# prc20breakout.net
KiCad netlist of a schematic drawn in EAGLE
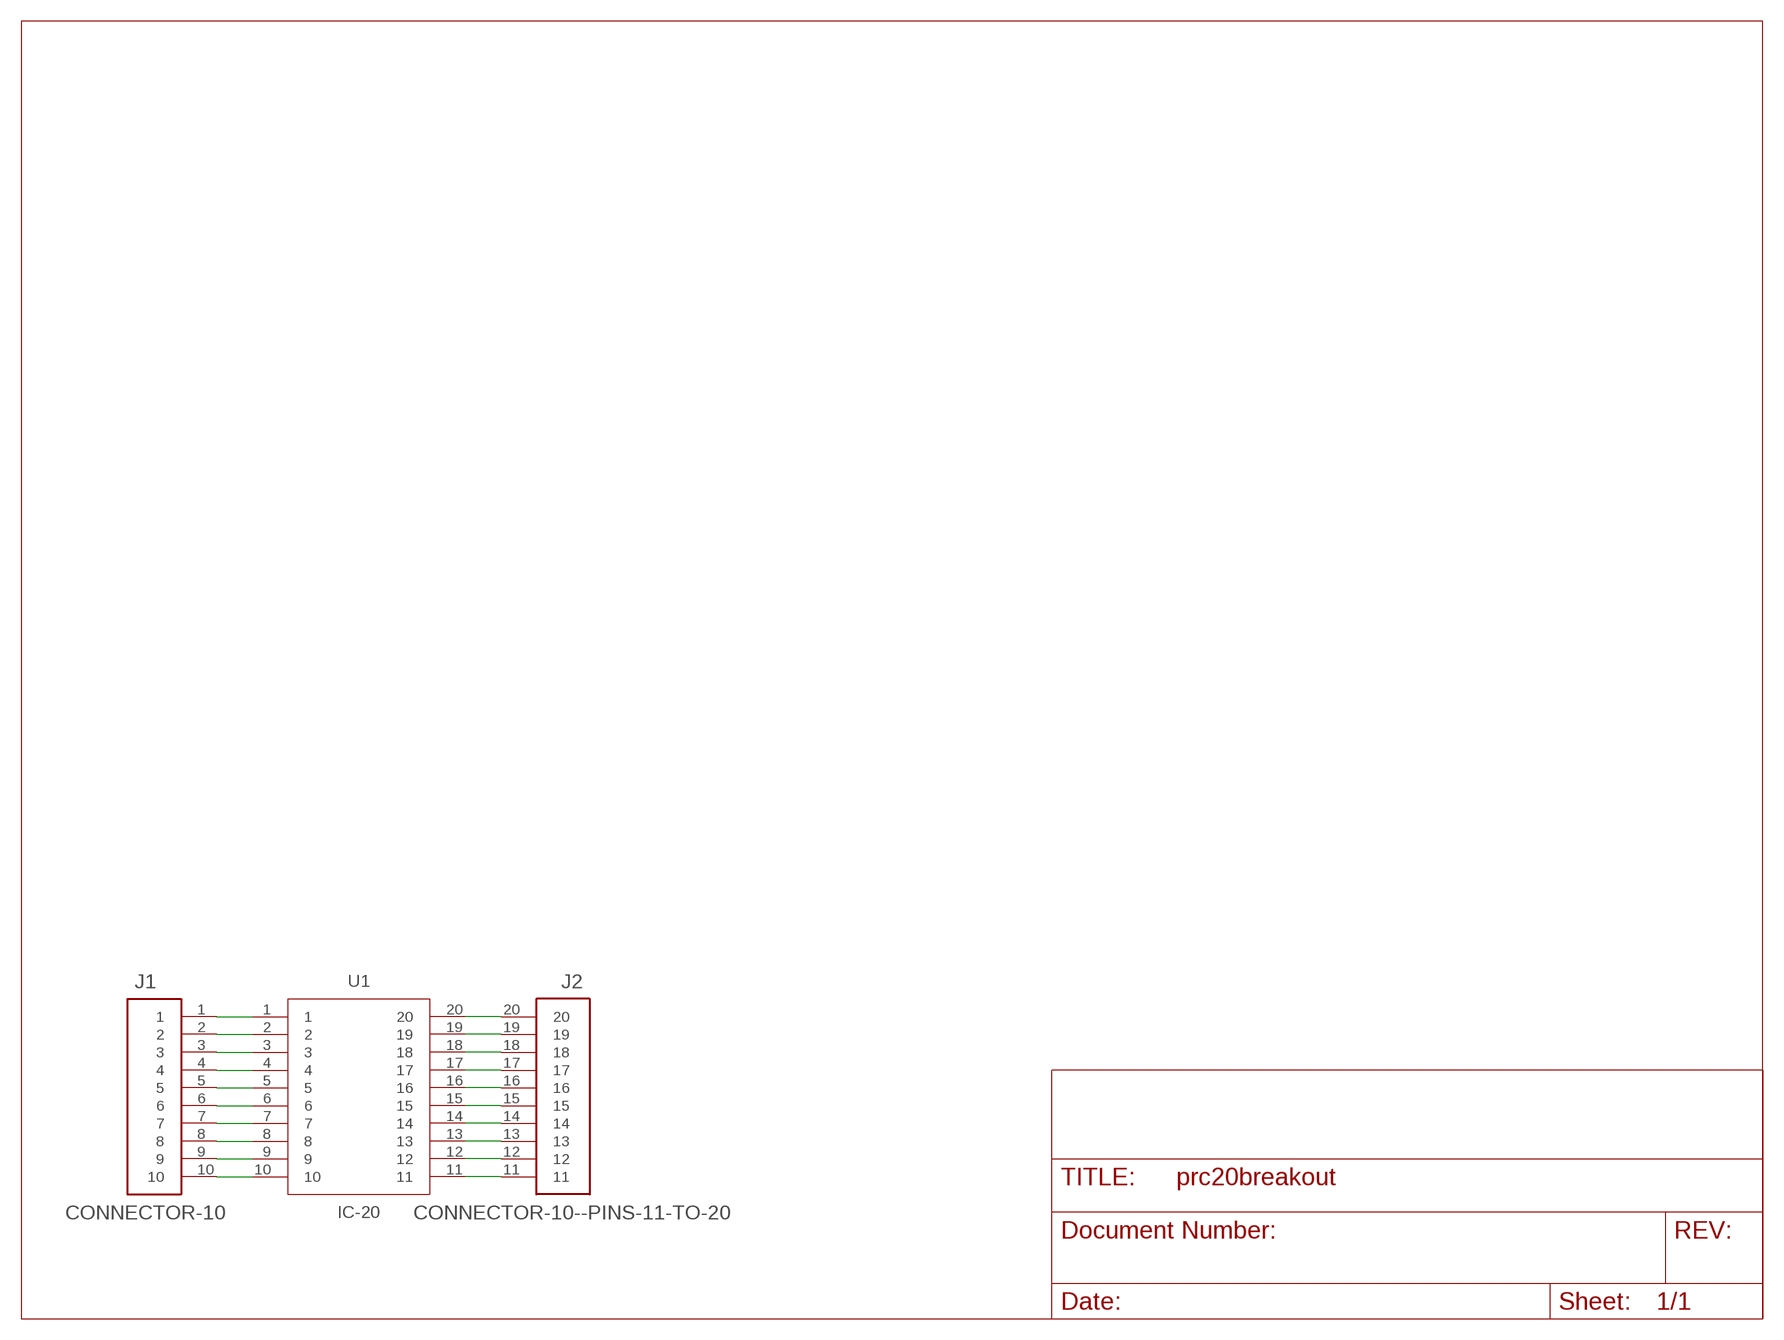
[diagram p0: schematic, sheet 1]

(export (version "E")
  (design (tool "Eeschema 10.0.6"))
  (components
    (comp (ref "J1")
      (value "CONNECTOR-10")
      (footprint "eagle-import:ESQ-110-XX-XX-S")
      (libsource (lib "eagle-import") (part "CONNECTOR-10"))
    )
    (comp (ref "J2")
      (value "CONNECTOR-10--PINS-11-TO-20")
      (footprint "eagle-import:ESQ-110-XX-XX-S--ROUND-PIN-1")
      (libsource (lib "eagle-import") (part "CONNECTOR-10--PINS-11-TO-20"))
    )
    (comp (ref "U1")
      (value "IC-20")
      (footprint "eagle-import:PLCC127P990X990X457-20N")
      (libsource (lib "eagle-import") (part "IC-20"))
    )
  )
  (nets
    (net (code "1") (name "Net-(J1-Pad1)") (class "Default")
      (node (ref "J1") (pin "1") (pinfunction "1_1") (pintype "bidirectional"))
      (node (ref "U1") (pin "1") (pinfunction "1_1") (pintype "bidirectional"))
    )
    (net (code "2") (name "Net-(J1-Pad2)") (class "Default")
      (node (ref "J1") (pin "2") (pinfunction "2_2") (pintype "bidirectional"))
      (node (ref "U1") (pin "2") (pinfunction "2_2") (pintype "bidirectional"))
    )
    (net (code "3") (name "Net-(J1-Pad3)") (class "Default")
      (node (ref "J1") (pin "3") (pinfunction "3_3") (pintype "bidirectional"))
      (node (ref "U1") (pin "3") (pinfunction "3_3") (pintype "bidirectional"))
    )
    (net (code "4") (name "Net-(J1-Pad4)") (class "Default")
      (node (ref "J1") (pin "4") (pinfunction "4_4") (pintype "bidirectional"))
      (node (ref "U1") (pin "4") (pinfunction "4_4") (pintype "bidirectional"))
    )
    (net (code "5") (name "Net-(J1-Pad5)") (class "Default")
      (node (ref "J1") (pin "5") (pinfunction "5_5") (pintype "bidirectional"))
      (node (ref "U1") (pin "5") (pinfunction "5_5") (pintype "bidirectional"))
    )
    (net (code "6") (name "Net-(J1-Pad6)") (class "Default")
      (node (ref "J1") (pin "6") (pinfunction "6_6") (pintype "bidirectional"))
      (node (ref "U1") (pin "6") (pinfunction "6_6") (pintype "bidirectional"))
    )
    (net (code "7") (name "Net-(J1-Pad7)") (class "Default")
      (node (ref "J1") (pin "7") (pinfunction "7_7") (pintype "bidirectional"))
      (node (ref "U1") (pin "7") (pinfunction "7_7") (pintype "bidirectional"))
    )
    (net (code "8") (name "Net-(J1-Pad8)") (class "Default")
      (node (ref "J1") (pin "8") (pinfunction "8_8") (pintype "bidirectional"))
      (node (ref "U1") (pin "8") (pinfunction "8_8") (pintype "bidirectional"))
    )
    (net (code "9") (name "Net-(J1-Pad9)") (class "Default")
      (node (ref "J1") (pin "9") (pinfunction "9_9") (pintype "bidirectional"))
      (node (ref "U1") (pin "9") (pinfunction "9_9") (pintype "bidirectional"))
    )
    (net (code "10") (name "Net-(J1-Pad10)") (class "Default")
      (node (ref "J1") (pin "10") (pinfunction "10_10") (pintype "bidirectional"))
      (node (ref "U1") (pin "10") (pinfunction "10_10") (pintype "bidirectional"))
    )
    (net (code "11") (name "Net-(J2-Pad11)") (class "Default")
      (node (ref "J2") (pin "11") (pinfunction "11_11") (pintype "bidirectional"))
      (node (ref "U1") (pin "11") (pinfunction "11_11") (pintype "bidirectional"))
    )
    (net (code "12") (name "Net-(J2-Pad12)") (class "Default")
      (node (ref "J2") (pin "12") (pinfunction "12_12") (pintype "bidirectional"))
      (node (ref "U1") (pin "12") (pinfunction "12_12") (pintype "bidirectional"))
    )
    (net (code "13") (name "Net-(J2-Pad13)") (class "Default")
      (node (ref "J2") (pin "13") (pinfunction "13_13") (pintype "bidirectional"))
      (node (ref "U1") (pin "13") (pinfunction "13_13") (pintype "bidirectional"))
    )
    (net (code "14") (name "Net-(J2-Pad14)") (class "Default")
      (node (ref "J2") (pin "14") (pinfunction "14_14") (pintype "bidirectional"))
      (node (ref "U1") (pin "14") (pinfunction "14_14") (pintype "bidirectional"))
    )
    (net (code "15") (name "Net-(J2-Pad15)") (class "Default")
      (node (ref "J2") (pin "15") (pinfunction "15_15") (pintype "bidirectional"))
      (node (ref "U1") (pin "15") (pinfunction "15_15") (pintype "bidirectional"))
    )
    (net (code "16") (name "Net-(J2-Pad16)") (class "Default")
      (node (ref "J2") (pin "16") (pinfunction "16_16") (pintype "bidirectional"))
      (node (ref "U1") (pin "16") (pinfunction "16_16") (pintype "bidirectional"))
    )
    (net (code "17") (name "Net-(J2-Pad17)") (class "Default")
      (node (ref "J2") (pin "17") (pinfunction "17_17") (pintype "bidirectional"))
      (node (ref "U1") (pin "17") (pinfunction "17_17") (pintype "bidirectional"))
    )
    (net (code "18") (name "Net-(J2-Pad18)") (class "Default")
      (node (ref "J2") (pin "18") (pinfunction "18_18") (pintype "bidirectional"))
      (node (ref "U1") (pin "18") (pinfunction "18_18") (pintype "bidirectional"))
    )
    (net (code "19") (name "Net-(J2-Pad19)") (class "Default")
      (node (ref "J2") (pin "19") (pinfunction "19_19") (pintype "bidirectional"))
      (node (ref "U1") (pin "19") (pinfunction "19_19") (pintype "bidirectional"))
    )
    (net (code "20") (name "Net-(J2-Pad20)") (class "Default")
      (node (ref "J2") (pin "20") (pinfunction "20_20") (pintype "bidirectional"))
      (node (ref "U1") (pin "20") (pinfunction "20_20") (pintype "bidirectional"))
    )
  )
)
